# Fan-Module.net
KiCad netlist of a schematic drawn in EAGLE
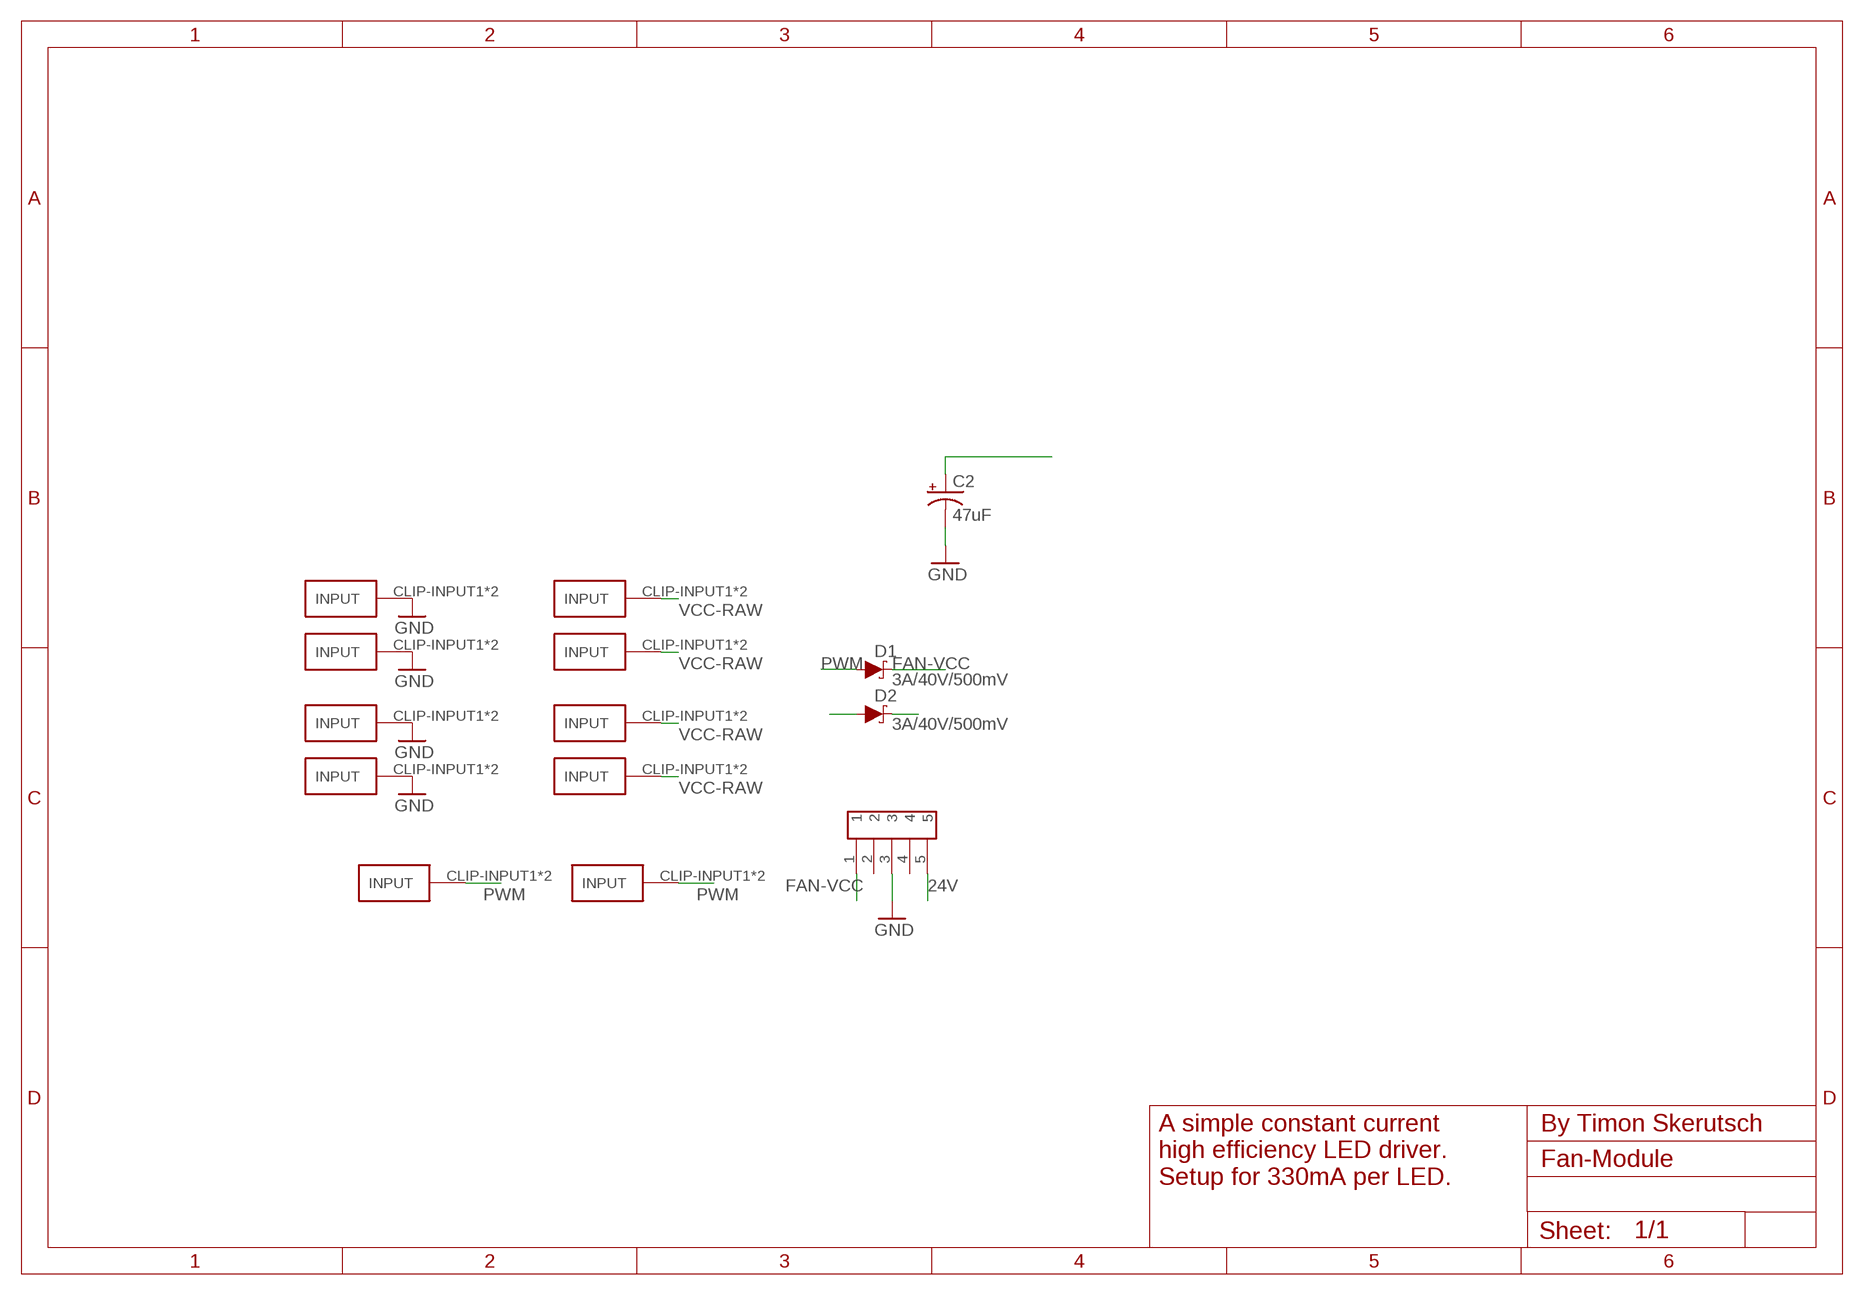
[diagram p0: schematic, sheet 1]

(export (version "E")
  (design (tool "Eeschema 10.0.6"))
  (components
    (comp (ref "C2")
      (value "47uF")
      (footprint "eagle-import:PANASONIC_D")
      (libsource (lib "eagle-import") (part "47UF-POLAR-PANASONIC_D-35V-20%"))
    )
    (comp (ref "D1")
      (value "3A/40V/500mV")
      (footprint "eagle-import:SMA-DIODE")
      (libsource (lib "eagle-import") (part "DIODE-SCHOTTKY-B340A"))
    )
    (comp (ref "D2")
      (value "3A/40V/500mV")
      (footprint "eagle-import:SMA-DIODE")
      (libsource (lib "eagle-import") (part "DIODE-SCHOTTKY-B340A"))
    )
    (comp (ref "GND-CLIP")
      (value "FUSE-HOLDER-5X20MM")
      (footprint "eagle-import:FUSE-HOLDER-5X20MM")
      (libsource (lib "eagle-import") (part "FUSE-HOLDER-5X20MM"))
    )
    (comp (ref "GND-CLIP1")
      (value "FUSE-HOLDER-5X20MM")
      (footprint "eagle-import:FUSE-HOLDER-5X20MM")
      (libsource (lib "eagle-import") (part "FUSE-HOLDER-5X20MM"))
    )
    (comp (ref "GND-CLIP2")
      (value "FUSE-HOLDER-5X20MM")
      (footprint "eagle-import:FUSE-HOLDER-5X20MM")
      (libsource (lib "eagle-import") (part "FUSE-HOLDER-5X20MM"))
    )
    (comp (ref "GND-CLIP3")
      (value "FUSE-HOLDER-5X20MM")
      (footprint "eagle-import:FUSE-HOLDER-5X20MM")
      (libsource (lib "eagle-import") (part "FUSE-HOLDER-5X20MM"))
    )
    (comp (ref "PWM-CLIP")
      (value "FUSE-HOLDER-5X20MM")
      (footprint "eagle-import:FUSE-HOLDER-5X20MM")
      (libsource (lib "eagle-import") (part "FUSE-HOLDER-5X20MM"))
    )
    (comp (ref "PWM-CLIP1")
      (value "FUSE-HOLDER-5X20MM")
      (footprint "eagle-import:FUSE-HOLDER-5X20MM")
      (libsource (lib "eagle-import") (part "FUSE-HOLDER-5X20MM"))
    )
    (comp (ref "U$2")
      (value "M20-8900505")
      (footprint "eagle-import:M20-8900505")
      (libsource (lib "eagle-import") (part "M20-8900505"))
    )
    (comp (ref "VCC-CLIP")
      (value "FUSE-HOLDER-5X20MM")
      (footprint "eagle-import:FUSE-HOLDER-5X20MM")
      (libsource (lib "eagle-import") (part "FUSE-HOLDER-5X20MM"))
    )
    (comp (ref "VCC-CLIP1")
      (value "FUSE-HOLDER-5X20MM")
      (footprint "eagle-import:FUSE-HOLDER-5X20MM")
      (libsource (lib "eagle-import") (part "FUSE-HOLDER-5X20MM"))
    )
    (comp (ref "VCC-CLIP2")
      (value "FUSE-HOLDER-5X20MM")
      (footprint "eagle-import:FUSE-HOLDER-5X20MM")
      (libsource (lib "eagle-import") (part "FUSE-HOLDER-5X20MM"))
    )
    (comp (ref "VCC-CLIP3")
      (value "FUSE-HOLDER-5X20MM")
      (footprint "eagle-import:FUSE-HOLDER-5X20MM")
      (libsource (lib "eagle-import") (part "FUSE-HOLDER-5X20MM"))
    )
  )
  (nets
    (net (code "1") (name "/24V") (class "Default")
      (node (ref "D2") (pin "C") (pinfunction "C_C") (pintype "passive"))
      (node (ref "U$2") (pin "5") (pinfunction "5_5") (pintype "bidirectional"))
    )
    (net (code "2") (name "/FAN-VCC") (class "Default")
      (node (ref "C2") (pin "+") (pinfunction "+_+") (pintype "passive"))
      (node (ref "D1") (pin "C") (pinfunction "C_C") (pintype "passive"))
      (node (ref "U$2") (pin "1") (pinfunction "1_1") (pintype "bidirectional"))
    )
    (net (code "3") (name "/PWM") (class "Default")
      (node (ref "D1") (pin "A") (pinfunction "A_A") (pintype "passive"))
      (node (ref "PWM-CLIP") (pin "CLIP-INPUT1") (pinfunction "INPUT_CLIP-INPUT1") (pintype "bidirectional"))
      (node (ref "PWM-CLIP") (pin "CLIP-INPUT2") (pinfunction "INPUT_CLIP-INPUT2") (pintype "bidirectional"))
      (node (ref "PWM-CLIP1") (pin "CLIP-INPUT1") (pinfunction "INPUT_CLIP-INPUT1") (pintype "bidirectional"))
      (node (ref "PWM-CLIP1") (pin "CLIP-INPUT2") (pinfunction "INPUT_CLIP-INPUT2") (pintype "bidirectional"))
    )
    (net (code "4") (name "/VCC-RAW") (class "Default")
      (node (ref "D2") (pin "A") (pinfunction "A_A") (pintype "passive"))
      (node (ref "VCC-CLIP") (pin "CLIP-INPUT1") (pinfunction "INPUT_CLIP-INPUT1") (pintype "bidirectional"))
      (node (ref "VCC-CLIP") (pin "CLIP-INPUT2") (pinfunction "INPUT_CLIP-INPUT2") (pintype "bidirectional"))
      (node (ref "VCC-CLIP1") (pin "CLIP-INPUT1") (pinfunction "INPUT_CLIP-INPUT1") (pintype "bidirectional"))
      (node (ref "VCC-CLIP1") (pin "CLIP-INPUT2") (pinfunction "INPUT_CLIP-INPUT2") (pintype "bidirectional"))
      (node (ref "VCC-CLIP2") (pin "CLIP-INPUT1") (pinfunction "INPUT_CLIP-INPUT1") (pintype "bidirectional"))
      (node (ref "VCC-CLIP2") (pin "CLIP-INPUT2") (pinfunction "INPUT_CLIP-INPUT2") (pintype "bidirectional"))
      (node (ref "VCC-CLIP3") (pin "CLIP-INPUT1") (pinfunction "INPUT_CLIP-INPUT1") (pintype "bidirectional"))
      (node (ref "VCC-CLIP3") (pin "CLIP-INPUT2") (pinfunction "INPUT_CLIP-INPUT2") (pintype "bidirectional"))
    )
    (net (code "5") (name "GND") (class "Default")
      (node (ref "C2") (pin "-") (pinfunction "-_-") (pintype "passive"))
      (node (ref "GND-CLIP") (pin "CLIP-INPUT1") (pinfunction "INPUT_CLIP-INPUT1") (pintype "bidirectional"))
      (node (ref "GND-CLIP") (pin "CLIP-INPUT2") (pinfunction "INPUT_CLIP-INPUT2") (pintype "bidirectional"))
      (node (ref "GND-CLIP1") (pin "CLIP-INPUT1") (pinfunction "INPUT_CLIP-INPUT1") (pintype "bidirectional"))
      (node (ref "GND-CLIP1") (pin "CLIP-INPUT2") (pinfunction "INPUT_CLIP-INPUT2") (pintype "bidirectional"))
      (node (ref "GND-CLIP2") (pin "CLIP-INPUT1") (pinfunction "INPUT_CLIP-INPUT1") (pintype "bidirectional"))
      (node (ref "GND-CLIP2") (pin "CLIP-INPUT2") (pinfunction "INPUT_CLIP-INPUT2") (pintype "bidirectional"))
      (node (ref "GND-CLIP3") (pin "CLIP-INPUT1") (pinfunction "INPUT_CLIP-INPUT1") (pintype "bidirectional"))
      (node (ref "GND-CLIP3") (pin "CLIP-INPUT2") (pinfunction "INPUT_CLIP-INPUT2") (pintype "bidirectional"))
      (node (ref "U$2") (pin "3") (pinfunction "3_3") (pintype "bidirectional"))
    )
    (net (code "6") (name "unconnected-(U$2-Pad2)") (class "Default")
      (node (ref "U$2") (pin "2") (pinfunction "2_2") (pintype "bidirectional"))
    )
    (net (code "7") (name "unconnected-(U$2-Pad4)") (class "Default")
      (node (ref "U$2") (pin "4") (pinfunction "4_4") (pintype "bidirectional"))
    )
  )
)
